# Leds.net
KiCad netlist of a schematic drawn in EAGLE
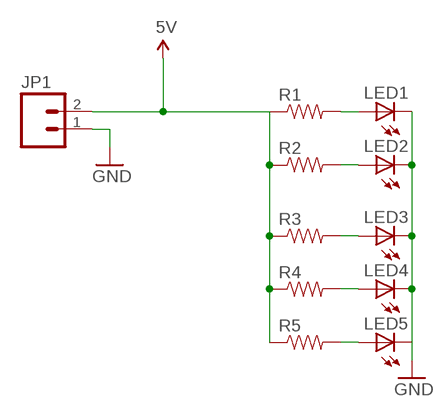
[diagram p0: schematic, sheet 1]

(export (version "E")
  (design (tool "Eeschema 10.0.6"))
  (components
    (comp (ref "JP1")
      (value "M02LOCK_LONGPADS")
      (footprint "eagle-import:1X02_LOCK_LONGPADS")
      (libsource (lib "eagle-import") (part "M02LOCK_LONGPADS"))
    )
    (comp (ref "LED1")
      (value "LED5MM")
      (footprint "eagle-import:LED5MM")
      (libsource (lib "eagle-import") (part "LED5MM"))
    )
    (comp (ref "LED2")
      (value "LED5MM")
      (footprint "eagle-import:LED5MM")
      (libsource (lib "eagle-import") (part "LED5MM"))
    )
    (comp (ref "LED3")
      (value "LED5MM")
      (footprint "eagle-import:LED5MM")
      (libsource (lib "eagle-import") (part "LED5MM"))
    )
    (comp (ref "LED4")
      (value "LED5MM")
      (footprint "eagle-import:LED5MM")
      (libsource (lib "eagle-import") (part "LED5MM"))
    )
    (comp (ref "LED5")
      (value "LED5MM")
      (footprint "eagle-import:LED5MM")
      (libsource (lib "eagle-import") (part "LED5MM"))
    )
    (comp (ref "R1")
      (value "RESISTOR0805-RES")
      (footprint "eagle-import:0805")
      (libsource (lib "eagle-import") (part "RESISTOR0805-RES"))
    )
    (comp (ref "R2")
      (value "RESISTOR0805-RES")
      (footprint "eagle-import:0805")
      (libsource (lib "eagle-import") (part "RESISTOR0805-RES"))
    )
    (comp (ref "R3")
      (value "RESISTOR0805-RES")
      (footprint "eagle-import:0805")
      (libsource (lib "eagle-import") (part "RESISTOR0805-RES"))
    )
    (comp (ref "R4")
      (value "RESISTOR0805-RES")
      (footprint "eagle-import:0805")
      (libsource (lib "eagle-import") (part "RESISTOR0805-RES"))
    )
    (comp (ref "R5")
      (value "RESISTOR0805-RES")
      (footprint "eagle-import:0805")
      (libsource (lib "eagle-import") (part "RESISTOR0805-RES"))
    )
  )
  (nets
    (net (code "1") (name "5V") (class "Default")
      (node (ref "JP1") (pin "2") (pinfunction "2_2") (pintype "passive"))
      (node (ref "R1") (pin "1") (pinfunction "1_1") (pintype "passive"))
      (node (ref "R2") (pin "1") (pinfunction "1_1") (pintype "passive"))
      (node (ref "R3") (pin "1") (pinfunction "1_1") (pintype "passive"))
      (node (ref "R4") (pin "1") (pinfunction "1_1") (pintype "passive"))
      (node (ref "R5") (pin "1") (pinfunction "1_1") (pintype "passive"))
    )
    (net (code "2") (name "GND") (class "Default")
      (node (ref "JP1") (pin "1") (pinfunction "1_1") (pintype "passive"))
      (node (ref "LED1") (pin "K") (pinfunction "C_K") (pintype "passive"))
      (node (ref "LED2") (pin "K") (pinfunction "C_K") (pintype "passive"))
      (node (ref "LED3") (pin "K") (pinfunction "C_K") (pintype "passive"))
      (node (ref "LED4") (pin "K") (pinfunction "C_K") (pintype "passive"))
      (node (ref "LED5") (pin "K") (pinfunction "C_K") (pintype "passive"))
    )
    (net (code "3") (name "Net-(LED1-PadA)") (class "Default")
      (node (ref "LED1") (pin "A") (pinfunction "A_A") (pintype "passive"))
      (node (ref "R1") (pin "2") (pinfunction "2_2") (pintype "passive"))
    )
    (net (code "4") (name "Net-(LED2-PadA)") (class "Default")
      (node (ref "LED2") (pin "A") (pinfunction "A_A") (pintype "passive"))
      (node (ref "R2") (pin "2") (pinfunction "2_2") (pintype "passive"))
    )
    (net (code "5") (name "Net-(LED3-PadA)") (class "Default")
      (node (ref "LED3") (pin "A") (pinfunction "A_A") (pintype "passive"))
      (node (ref "R3") (pin "2") (pinfunction "2_2") (pintype "passive"))
    )
    (net (code "6") (name "Net-(LED4-PadA)") (class "Default")
      (node (ref "LED4") (pin "A") (pinfunction "A_A") (pintype "passive"))
      (node (ref "R4") (pin "2") (pinfunction "2_2") (pintype "passive"))
    )
    (net (code "7") (name "Net-(LED5-PadA)") (class "Default")
      (node (ref "LED5") (pin "A") (pinfunction "A_A") (pintype "passive"))
      (node (ref "R5") (pin "2") (pinfunction "2_2") (pintype "passive"))
    )
  )
)
